# AuArd_1.net
KiCad netlist of a schematic drawn in Altium Designer
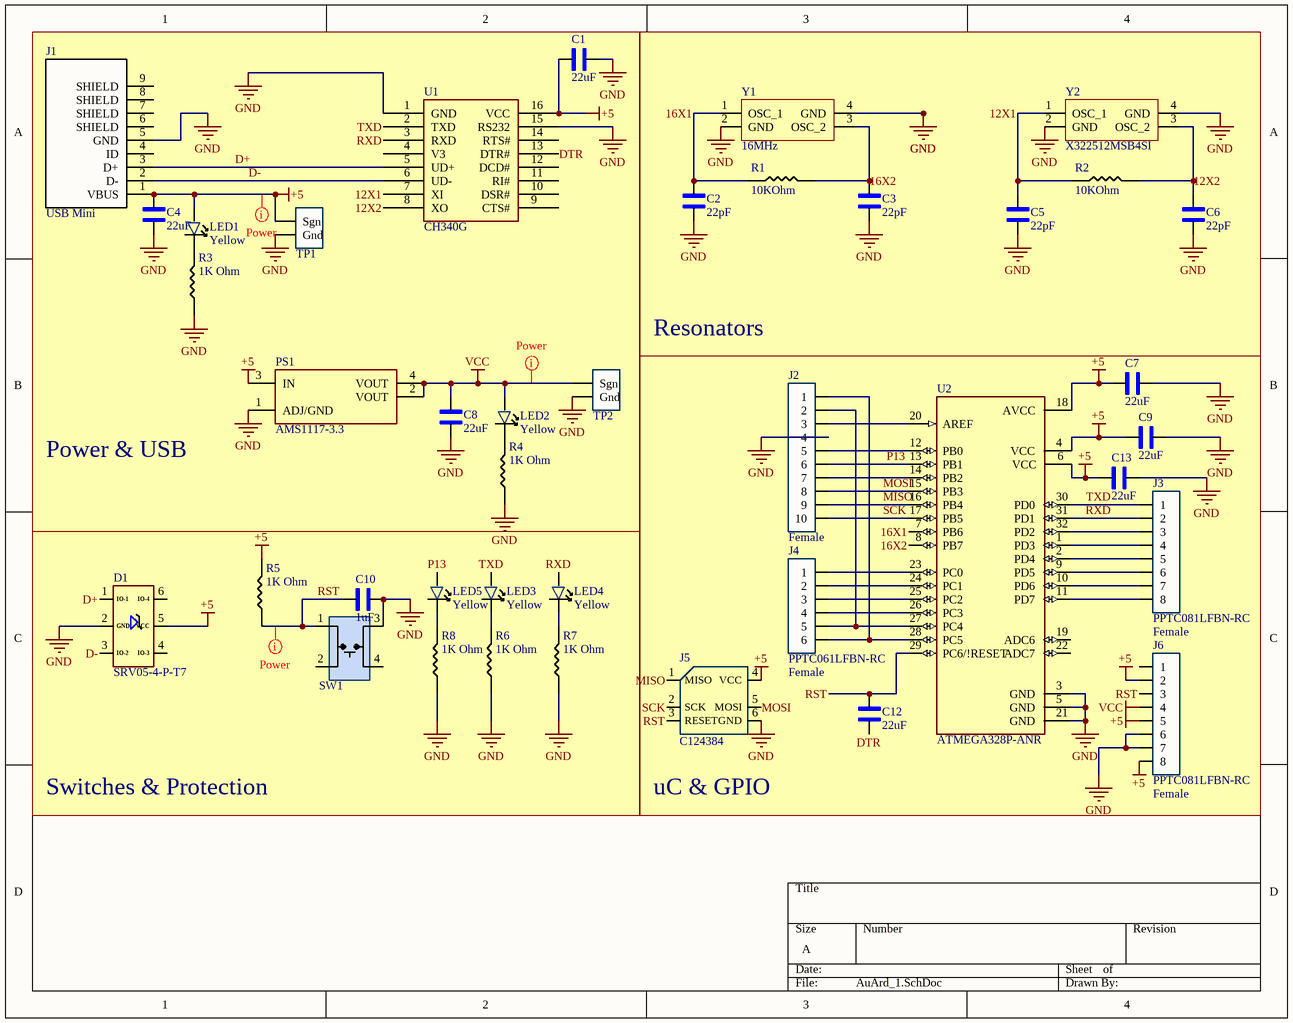
[diagram p0: AuArd_1.SchDoc]

(export (version "E")
  (design (tool "Eeschema 10.0.6"))
  (components
    (comp (ref "C1")
      (value "22uF")
      (footprint "1206_Passive_Capacitor")
      (description "22uF ±10% 25V X5R 1206 Multilayer Ceramic Capacitors MLCC - SMD/SMT RoHS")
      (fields (field (name "MFR PART #") "CL31A226KAHNNNE") (field (name "LCSC PART#") "C12891"))
      (libsource (lib "ECEN5730Lib_JLC_2021_08") (part "C_22uF_1206"))
    )
    (comp (ref "C2")
      (value "22pF")
      (footprint "1206_Passive_Capacitor")
      (description "22pF ±5% 1kV C0G 1206 Multilayer Ceramic Capacitors MLCC - SMD/SMT RoHS")
      (fields (field (name "LCSC PART#") "C313096") (field (name "MFR PART #") "1206CG220J102NT"))
      (libsource (lib "ECEN5730Lib_JLC_2021_08") (part "C_22pF_1206"))
    )
    (comp (ref "C3")
      (value "22pF")
      (footprint "1206_Passive_Capacitor")
      (description "22pF ±5% 1kV C0G 1206 Multilayer Ceramic Capacitors MLCC - SMD/SMT RoHS")
      (fields (field (name "LCSC PART#") "C313096") (field (name "MFR PART #") "1206CG220J102NT"))
      (libsource (lib "ECEN5730Lib_JLC_2021_08") (part "C_22pF_1206"))
    )
    (comp (ref "C4")
      (value "22uF")
      (footprint "1206_Passive_Capacitor")
      (description "22uF ±10% 25V X5R 1206 Multilayer Ceramic Capacitors MLCC - SMD/SMT RoHS")
      (fields (field (name "MFR PART #") "CL31A226KAHNNNE") (field (name "LCSC PART#") "C12891"))
      (libsource (lib "ECEN5730Lib_JLC_2021_08") (part "C_22uF_1206"))
    )
    (comp (ref "C5")
      (value "22pF")
      (footprint "1206_Passive_Capacitor")
      (description "22pF ±5% 1kV C0G 1206 Multilayer Ceramic Capacitors MLCC - SMD/SMT RoHS")
      (fields (field (name "LCSC PART#") "C313096") (field (name "MFR PART #") "1206CG220J102NT"))
      (libsource (lib "ECEN5730Lib_JLC_2021_08") (part "C_22pF_1206"))
    )
    (comp (ref "C6")
      (value "22pF")
      (footprint "1206_Passive_Capacitor")
      (description "22pF ±5% 1kV C0G 1206 Multilayer Ceramic Capacitors MLCC - SMD/SMT RoHS")
      (fields (field (name "LCSC PART#") "C313096") (field (name "MFR PART #") "1206CG220J102NT"))
      (libsource (lib "ECEN5730Lib_JLC_2021_08") (part "C_22pF_1206"))
    )
    (comp (ref "C7")
      (value "22uF")
      (footprint "1206_Passive_Capacitor")
      (description "22uF ±10% 25V X5R 1206 Multilayer Ceramic Capacitors MLCC - SMD/SMT RoHS")
      (fields (field (name "MFR PART #") "CL31A226KAHNNNE") (field (name "LCSC PART#") "C12891"))
      (libsource (lib "ECEN5730Lib_JLC_2021_08") (part "C_22uF_1206"))
    )
    (comp (ref "C8")
      (value "22uF")
      (footprint "1206_Passive_Capacitor")
      (description "22uF ±10% 25V X5R 1206 Multilayer Ceramic Capacitors MLCC - SMD/SMT RoHS")
      (fields (field (name "MFR PART #") "CL31A226KAHNNNE") (field (name "LCSC PART#") "C12891"))
      (libsource (lib "ECEN5730Lib_JLC_2021_08") (part "C_22uF_1206"))
    )
    (comp (ref "C9")
      (value "22uF")
      (footprint "1206_Passive_Capacitor")
      (description "22uF ±10% 25V X5R 1206 Multilayer Ceramic Capacitors MLCC - SMD/SMT RoHS")
      (fields (field (name "MFR PART #") "CL31A226KAHNNNE") (field (name "LCSC PART#") "C12891"))
      (libsource (lib "ECEN5730Lib_JLC_2021_08") (part "C_22uF_1206"))
    )
    (comp (ref "C10")
      (value "1uF")
      (footprint "1206_Passive_Capacitor")
      (description "MULTILAYER CERAMIC CAPACITORS MLCC - SMD/SMT 1UF 50V 1206 ROHS")
      (fields (field (name "DIGIKEY PART") "399-8150-1-ND") (field (name "MFR PART #") "CL31B105KBHNNNE"))
      (libsource (lib "ECEN5730Lib_JLC_2021_08") (part "C_1uF_1206"))
    )
    (comp (ref "C12")
      (value "22uF")
      (footprint "1206_Passive_Capacitor")
      (description "22uF ±10% 25V X5R 1206 Multilayer Ceramic Capacitors MLCC - SMD/SMT RoHS")
      (fields (field (name "MFR PART #") "CL31A226KAHNNNE") (field (name "LCSC PART#") "C12891"))
      (libsource (lib "ECEN5730Lib_JLC_2021_08") (part "C_22uF_1206"))
    )
    (comp (ref "C13")
      (value "22uF")
      (footprint "1206_Passive_Capacitor")
      (description "22uF ±10% 25V X5R 1206 Multilayer Ceramic Capacitors MLCC - SMD/SMT RoHS")
      (fields (field (name "MFR PART #") "CL31A226KAHNNNE") (field (name "LCSC PART#") "C12891"))
      (libsource (lib "ECEN5730Lib_JLC_2021_08") (part "C_22uF_1206"))
    )
    (comp (ref "D1")
      (value "SRV05-4-P-T7")
      (footprint "TVS")
      (description "TVS SOT-23-6 ROHS")
      (fields (field (name "LCSC PART#") "C85364"))
      (libsource (lib "ECEN5730Lib_JLC_2021_08") (part "D_TVS_Diode"))
    )
    (comp (ref "J1")
      (value "USB Mini")
      (footprint "USB_MINI_B")
      (description "Through Hole USB Connectors RoHS")
      (fields (field (name "LCSC PART#") "C46398") (field (name "MFR PART #") "920-462A2021D10102"))
      (libsource (lib "ECEN5730Lib_JLC_2021_08") (part "J_USB_B_Mini"))
    )
    (comp (ref "J2")
      (value "Female")
      (footprint "10_PIN_ARDUINO_100MIL")
      (description "10 Position Header Connector 0.100\" (2.54mm) Through Hole Tin")
      (fields (field (name "DIGIKEY PART") "S7008-ND") (field (name "LCSC PART#") "C225507"))
      (libsource (lib "ECEN5730Lib_JLC_2021_08") (part "JF_10_PIN_FEMALE_ARDUINO"))
    )
    (comp (ref "J3")
      (value "PPTC081LFBN-RC")
      (footprint "8_PIN_ARDUINO_100MIL")
      (description "8 Position Header Connector 0.100\" (2.54mm) Through Hole Tin")
      (fields
        (field (name "DIGIKEY PART") "S7006-ND")
        (field (name "LCSC PART#") "C27438")
        (field (name "ALTIUM_VALUE") "Female")
      )
      (libsource (lib "ECEN5730Lib_JLC_2021_08") (part "JF_8_PIN_FEMALE_ARDUINO"))
    )
    (comp (ref "J4")
      (value "PPTC061LFBN-RC")
      (footprint "6_PIN_ARDUINO_100mil")
      (description "6 Position Header Connector 0.100\" (2.54mm) Through Hole Tin")
      (fields
        (field (name "DIGIKEY PART") "S7004-ND")
        (field (name "LCSC PART#") "C40877")
        (field (name "ALTIUM_VALUE") "Female")
      )
      (libsource (lib "ECEN5730Lib_JLC_2021_08") (part "JF_6_PIN_FEMALE_ARDUINO"))
    )
    (comp (ref "J5")
      (value "NRPN032PAEN-RC")
      (footprint "ICSP")
      (description "Connector Header Through Hole 6 position 0.079\" (2.00mm)")
      (fields (field (name "DIGIKEY PART") "S5801-03-ND") (field (name "LCSC PART#") "C124384"))
      (libsource (lib "ECEN5730Lib_JLC_2021_08") (part "J_ICSP"))
    )
    (comp (ref "J6")
      (value "PPTC081LFBN-RC")
      (footprint "8_PIN_ARDUINO_100MIL")
      (description "8 Position Header Connector 0.100\" (2.54mm) Through Hole Tin")
      (fields
        (field (name "DIGIKEY PART") "S7006-ND")
        (field (name "LCSC PART#") "C27438")
        (field (name "ALTIUM_VALUE") "Female")
      )
      (libsource (lib "ECEN5730Lib_JLC_2021_08") (part "JF_8_PIN_FEMALE_ARDUINO"))
    )
    (comp (ref "LED1")
      (value "Yellow")
      (footprint "LED_0603")
      (description "LIGHT EMITTING DIODES (LED) YELLOW 585.5~591.5NM 90~180MCD@20MA TOP VIEW 0603 ROHS")
      (fields (field (name "MFR PART #") "19-213/Y2C-CQ2R2L/3T(CY)") (field (name "LCSC PART#") "C72038"))
      (libsource (lib "ECEN5730Lib_JLC_2021_08") (part "LED_YELLOW_0603"))
    )
    (comp (ref "LED2")
      (value "Yellow")
      (footprint "LED_0603")
      (description "LIGHT EMITTING DIODES (LED) YELLOW 585.5~591.5NM 90~180MCD@20MA TOP VIEW 0603 ROHS")
      (fields (field (name "MFR PART #") "19-213/Y2C-CQ2R2L/3T(CY)") (field (name "LCSC PART#") "C72038"))
      (libsource (lib "ECEN5730Lib_JLC_2021_08") (part "LED_YELLOW_0603"))
    )
    (comp (ref "LED3")
      (value "Yellow")
      (footprint "LED_0603")
      (description "LIGHT EMITTING DIODES (LED) YELLOW 585.5~591.5NM 90~180MCD@20MA TOP VIEW 0603 ROHS")
      (fields (field (name "MFR PART #") "19-213/Y2C-CQ2R2L/3T(CY)") (field (name "LCSC PART#") "C72038"))
      (libsource (lib "ECEN5730Lib_JLC_2021_08") (part "LED_YELLOW_0603"))
    )
    (comp (ref "LED4")
      (value "Yellow")
      (footprint "LED_0603")
      (description "LIGHT EMITTING DIODES (LED) YELLOW 585.5~591.5NM 90~180MCD@20MA TOP VIEW 0603 ROHS")
      (fields (field (name "MFR PART #") "19-213/Y2C-CQ2R2L/3T(CY)") (field (name "LCSC PART#") "C72038"))
      (libsource (lib "ECEN5730Lib_JLC_2021_08") (part "LED_YELLOW_0603"))
    )
    (comp (ref "LED5")
      (value "Yellow")
      (footprint "LED_0603")
      (description "LIGHT EMITTING DIODES (LED) YELLOW 585.5~591.5NM 90~180MCD@20MA TOP VIEW 0603 ROHS")
      (fields (field (name "MFR PART #") "19-213/Y2C-CQ2R2L/3T(CY)") (field (name "LCSC PART#") "C72038"))
      (libsource (lib "ECEN5730Lib_JLC_2021_08") (part "LED_YELLOW_0603"))
    )
    (comp (ref "PS1")
      (value "AMS1117-3.3")
      (footprint "LDO")
      (description "LOW DROPOUT REGULATORS(LDO) POSITIVE FIXED 1.3V @ 800MA 15V 3.3V 1A SOT-223 ROHS")
      (fields (field (name "LCSC PART#") "C6186"))
      (libsource (lib "ECEN5730Lib_JLC_2021_08") (part "PS_AMS_LDO_3v3"))
    )
    (comp (ref "R1")
      (value "10KOhm")
      (footprint "1206_Passive_Resitor")
      (description "10 kOhms ±5% 0.25W, 1/4W Chip Resistor 1206 (3216 Metric) Automotive AEC-Q200 Thick Film")
      (fields (field (name "DIGIKEY PART") "RMCF1206JT300RCT-ND") (field (name "LCSC PART#") "C17902"))
      (libsource (lib "ECEN5730Lib_JLC_2021_08") (part "R_10KOhm_1206"))
    )
    (comp (ref "R2")
      (value "10KOhm")
      (footprint "1206_Passive_Resitor")
      (description "10 kOhms ±5% 0.25W, 1/4W Chip Resistor 1206 (3216 Metric) Automotive AEC-Q200 Thick Film")
      (fields (field (name "DIGIKEY PART") "RMCF1206JT300RCT-ND") (field (name "LCSC PART#") "C17902"))
      (libsource (lib "ECEN5730Lib_JLC_2021_08") (part "R_10KOhm_1206"))
    )
    (comp (ref "R3")
      (value "1K Ohm")
      (footprint "1206_Passive_Resitor")
      (description "CHIP RESISTOR - SURFACE MOUNT 1KOHMS ±1% 1/4W 1206 ROHS")
      (fields (field (name "DIGIKEY PART") "RNCP1206FTD1K00CT-ND") (field (name "LCSC PART#") "C4410"))
      (libsource (lib "ECEN5730Lib_JLC_2021_08") (part "R_1K_1206"))
    )
    (comp (ref "R4")
      (value "1K Ohm")
      (footprint "1206_Passive_Resitor")
      (description "CHIP RESISTOR - SURFACE MOUNT 1KOHMS ±1% 1/4W 1206 ROHS")
      (fields (field (name "DIGIKEY PART") "RNCP1206FTD1K00CT-ND") (field (name "LCSC PART#") "C4410"))
      (libsource (lib "ECEN5730Lib_JLC_2021_08") (part "R_1K_1206"))
    )
    (comp (ref "R5")
      (value "1K Ohm")
      (footprint "1206_Passive_Resitor")
      (description "CHIP RESISTOR - SURFACE MOUNT 1KOHMS ±1% 1/4W 1206 ROHS")
      (fields (field (name "DIGIKEY PART") "RNCP1206FTD1K00CT-ND") (field (name "LCSC PART#") "C4410"))
      (libsource (lib "ECEN5730Lib_JLC_2021_08") (part "R_1K_1206"))
    )
    (comp (ref "R6")
      (value "1K Ohm")
      (footprint "1206_Passive_Resitor")
      (description "CHIP RESISTOR - SURFACE MOUNT 1KOHMS ±1% 1/4W 1206 ROHS")
      (fields (field (name "DIGIKEY PART") "RNCP1206FTD1K00CT-ND") (field (name "LCSC PART#") "C4410"))
      (libsource (lib "ECEN5730Lib_JLC_2021_08") (part "R_1K_1206"))
    )
    (comp (ref "R7")
      (value "1K Ohm")
      (footprint "1206_Passive_Resitor")
      (description "CHIP RESISTOR - SURFACE MOUNT 1KOHMS ±1% 1/4W 1206 ROHS")
      (fields (field (name "DIGIKEY PART") "RNCP1206FTD1K00CT-ND") (field (name "LCSC PART#") "C4410"))
      (libsource (lib "ECEN5730Lib_JLC_2021_08") (part "R_1K_1206"))
    )
    (comp (ref "R8")
      (value "1K Ohm")
      (footprint "1206_Passive_Resitor")
      (description "CHIP RESISTOR - SURFACE MOUNT 1KOHMS ±1% 1/4W 1206 ROHS")
      (fields (field (name "DIGIKEY PART") "RNCP1206FTD1K00CT-ND") (field (name "LCSC PART#") "C4410"))
      (libsource (lib "ECEN5730Lib_JLC_2021_08") (part "R_1K_1206"))
    )
    (comp (ref "SW1")
      (value "TL3305AF160QG")
      (footprint "Switch_JLC")
      (description "Tactile Switch SPST-NO Top Actuated Surface Mount")
      (fields (field (name "MFR PART #") "C174049"))
      (libsource (lib "ECEN5730Lib_JLC_2021_08") (part "SW_Push_Button_JLC"))
    )
    (comp (ref "TP1")
      (value "10x Probe TP")
      (footprint "TP10x_Probe")
      (description "Test Point 300 mil centers")
      (libsource (lib "ECEN5730Lib_Manual_2021_08") (part "TP_10x_Probe"))
    )
    (comp (ref "TP2")
      (value "10x Probe TP")
      (footprint "TP10x_Probe")
      (description "Test Point 300 mil centers")
      (libsource (lib "ECEN5730Lib_Manual_2021_08") (part "TP_10x_Probe"))
    )
    (comp (ref "U1")
      (value "CH340G")
      (footprint "USB to serial")
      (description "Transceiver USB 2.0 2Mbps SOP-16_150mil USB ICs RoHS")
      (fields (field (name "LCSC PART#") "C14267"))
      (libsource (lib "ECEN5730Lib_JLC_2021_08") (part "U_USBtoSerial"))
    )
    (comp (ref "U2")
      (value "ATMEGA328P-ANR")
      (footprint "ATMega328P")
      (description "AVR AVR® ATmega Microcontroller IC 8-Bit 20MHz 32KB (16K x 16) FLASH 32-TQFP (7x7)")
      (fields (field (name "MFR PART #") "ATMEGA328P-AU") (field (name "LCSC PART#") "C14877"))
      (libsource (lib "ECEN5730Lib_JLC_2021_08") (part "U_ATMega328P"))
    )
    (comp (ref "Y1")
      (value "16MHz")
      (footprint "Crystal resonator")
      (description "±10ppm 16000000Hz -40℃~85℃ 贴片无源晶振 60Ω 9pF SMD3225-4P Crystals ROHS")
      (fields (field (name "LCSC PART#") "C13738") (field (name "MFR PART #") "X322516MLB4SI"))
      (libsource (lib "ECEN5730Lib_JLC_2021_08") (part "X_16Mhz_Res"))
    )
    (comp (ref "Y2")
      (value "X322512MSB4SI")
      (footprint "Crystal resonator")
      (description "SMD Crystal Resonators 12MHz ±10ppm SMD-3225_4P RoHS")
      (fields (field (name "LCSC PART#") "C9002"))
      (libsource (lib "ECEN5730Lib_JLC_2021_08") (part "X_12MHz_Res"))
    )
  )
  (nets
    (net (code "1") (name "+5") (class "Default")
      (node (ref "C1") (pin "2") (pinfunction "2_2") (pintype "passive"))
      (node (ref "C13") (pin "2") (pinfunction "2_2") (pintype "passive"))
      (node (ref "C4") (pin "2") (pinfunction "2_2") (pintype "passive"))
      (node (ref "C7") (pin "2") (pinfunction "2_2") (pintype "passive"))
      (node (ref "C9") (pin "2") (pinfunction "2_2") (pintype "passive"))
      (node (ref "D1") (pin "5") (pinfunction "VCC_5") (pintype "passive"))
      (node (ref "J1") (pin "1") (pinfunction "VBUS_1") (pintype "passive"))
      (node (ref "J5") (pin "4") (pinfunction "VCC_4") (pintype "passive"))
      (node (ref "J6") (pin "2") (pinfunction "2_2") (pintype "passive"))
      (node (ref "J6") (pin "5") (pinfunction "5_5") (pintype "passive"))
      (node (ref "J6") (pin "8") (pinfunction "8_8") (pintype "passive"))
      (node (ref "LED1") (pin "1") (pinfunction "1_1") (pintype "passive"))
      (node (ref "PS1") (pin "3") (pinfunction "IN_3") (pintype "power_in"))
      (node (ref "R5") (pin "2") (pinfunction "2_2") (pintype "passive"))
      (node (ref "TP1") (pin "1") (pinfunction "Sgn_1") (pintype "passive"))
      (node (ref "U1") (pin "16") (pinfunction "VCC_16") (pintype "passive"))
      (node (ref "U2") (pin "18") (pinfunction "AVCC_18") (pintype "power_in"))
      (node (ref "U2") (pin "4") (pinfunction "VCC_4") (pintype "power_in"))
      (node (ref "U2") (pin "6") (pinfunction "VCC_6") (pintype "power_in"))
    )
    (net (code "2") (name "/12X1") (class "Default")
      (node (ref "C5") (pin "2") (pinfunction "2_2") (pintype "passive"))
      (node (ref "R2") (pin "1") (pinfunction "1_1") (pintype "passive"))
      (node (ref "U1") (pin "7") (pinfunction "XI_7") (pintype "passive"))
      (node (ref "Y2") (pin "1") (pinfunction "OSC_1_1") (pintype "passive"))
    )
    (net (code "3") (name "/12X2") (class "Default")
      (node (ref "C6") (pin "2") (pinfunction "2_2") (pintype "passive"))
      (node (ref "R2") (pin "2") (pinfunction "2_2") (pintype "passive"))
      (node (ref "U1") (pin "8") (pinfunction "XO_8") (pintype "passive"))
      (node (ref "Y2") (pin "3") (pinfunction "OSC_2_3") (pintype "passive"))
    )
    (net (code "4") (name "/16X1") (class "Default")
      (node (ref "C2") (pin "2") (pinfunction "2_2") (pintype "passive"))
      (node (ref "R1") (pin "1") (pinfunction "1_1") (pintype "passive"))
      (node (ref "U2") (pin "7") (pinfunction "PB6_7") (pintype "bidirectional"))
      (node (ref "Y1") (pin "1") (pinfunction "OSC_1_1") (pintype "passive"))
    )
    (net (code "5") (name "/16X2") (class "Default")
      (node (ref "C3") (pin "2") (pinfunction "2_2") (pintype "passive"))
      (node (ref "R1") (pin "2") (pinfunction "2_2") (pintype "passive"))
      (node (ref "U2") (pin "8") (pinfunction "PB7_8") (pintype "bidirectional"))
      (node (ref "Y1") (pin "3") (pinfunction "OSC_2_3") (pintype "passive"))
    )
    (net (code "6") (name "/D+") (class "Default")
      (node (ref "D1") (pin "1") (pinfunction "IO-1_1") (pintype "passive"))
      (node (ref "J1") (pin "3") (pinfunction "D+_3") (pintype "passive"))
      (node (ref "U1") (pin "5") (pinfunction "UD+_5") (pintype "passive"))
    )
    (net (code "7") (name "/D-") (class "Default")
      (node (ref "D1") (pin "3") (pinfunction "IO-2_3") (pintype "passive"))
      (node (ref "J1") (pin "2") (pinfunction "D-_2") (pintype "passive"))
      (node (ref "U1") (pin "6") (pinfunction "UD-_6") (pintype "passive"))
    )
    (net (code "8") (name "/DTR") (class "Default")
      (node (ref "C12") (pin "1") (pinfunction "1_1") (pintype "passive"))
      (node (ref "U1") (pin "13") (pinfunction "DTR#_13") (pintype "passive"))
    )
    (net (code "9") (name "/MISO") (class "Default")
      (node (ref "J2") (pin "9") (pinfunction "9_9") (pintype "passive"))
      (node (ref "J5") (pin "1") (pinfunction "MISO_1") (pintype "passive"))
      (node (ref "U2") (pin "16") (pinfunction "PB4_16") (pintype "bidirectional"))
    )
    (net (code "10") (name "/MOSI") (class "Default")
      (node (ref "J2") (pin "8") (pinfunction "8_8") (pintype "passive"))
      (node (ref "J5") (pin "5") (pinfunction "MOSI_5") (pintype "passive"))
      (node (ref "U2") (pin "15") (pinfunction "PB3_15") (pintype "bidirectional"))
    )
    (net (code "11") (name "/P13") (class "Default")
      (node (ref "J2") (pin "6") (pinfunction "6_6") (pintype "passive"))
      (node (ref "LED5") (pin "1") (pinfunction "1_1") (pintype "passive"))
      (node (ref "U2") (pin "13") (pinfunction "PB1_13") (pintype "bidirectional"))
    )
    (net (code "12") (name "/RST") (class "Default")
      (node (ref "C10") (pin "1") (pinfunction "1_1") (pintype "passive"))
      (node (ref "C12") (pin "2") (pinfunction "2_2") (pintype "passive"))
      (node (ref "J5") (pin "3") (pinfunction "RESET_3") (pintype "passive"))
      (node (ref "J6") (pin "3") (pinfunction "3_3") (pintype "passive"))
      (node (ref "R5") (pin "1") (pinfunction "1_1") (pintype "passive"))
      (node (ref "SW1") (pin "1") (pinfunction "1_1") (pintype "passive"))
      (node (ref "U2") (pin "29") (pinfunction "PC6/!RESET_29") (pintype "bidirectional"))
    )
    (net (code "13") (name "/RXD") (class "Default")
      (node (ref "J3") (pin "2") (pinfunction "2_2") (pintype "passive"))
      (node (ref "LED4") (pin "1") (pinfunction "1_1") (pintype "passive"))
      (node (ref "U1") (pin "3") (pinfunction "RXD_3") (pintype "passive"))
      (node (ref "U2") (pin "31") (pinfunction "PD1_31") (pintype "bidirectional"))
    )
    (net (code "14") (name "/SCK") (class "Default")
      (node (ref "J2") (pin "10") (pinfunction "10_10") (pintype "passive"))
      (node (ref "J5") (pin "2") (pinfunction "SCK_2") (pintype "passive"))
      (node (ref "U2") (pin "17") (pinfunction "PB5_17") (pintype "bidirectional"))
    )
    (net (code "15") (name "/TXD") (class "Default")
      (node (ref "J3") (pin "1") (pinfunction "1_1") (pintype "passive"))
      (node (ref "LED3") (pin "1") (pinfunction "1_1") (pintype "passive"))
      (node (ref "U1") (pin "2") (pinfunction "TXD_2") (pintype "passive"))
      (node (ref "U2") (pin "30") (pinfunction "PD0_30") (pintype "bidirectional"))
    )
    (net (code "16") (name "GND") (class "Default")
      (node (ref "C1") (pin "1") (pinfunction "1_1") (pintype "passive"))
      (node (ref "C10") (pin "2") (pinfunction "2_2") (pintype "passive"))
      (node (ref "C13") (pin "1") (pinfunction "1_1") (pintype "passive"))
      (node (ref "C2") (pin "1") (pinfunction "1_1") (pintype "passive"))
      (node (ref "C3") (pin "1") (pinfunction "1_1") (pintype "passive"))
      (node (ref "C4") (pin "1") (pinfunction "1_1") (pintype "passive"))
      (node (ref "C5") (pin "1") (pinfunction "1_1") (pintype "passive"))
      (node (ref "C6") (pin "1") (pinfunction "1_1") (pintype "passive"))
      (node (ref "C7") (pin "1") (pinfunction "1_1") (pintype "passive"))
      (node (ref "C8") (pin "1") (pinfunction "1_1") (pintype "passive"))
      (node (ref "C9") (pin "1") (pinfunction "1_1") (pintype "passive"))
      (node (ref "D1") (pin "2") (pinfunction "GND_2") (pintype "passive"))
      (node (ref "J1") (pin "5") (pinfunction "GND_5") (pintype "passive"))
      (node (ref "J2") (pin "4") (pinfunction "4_4") (pintype "passive"))
      (node (ref "J5") (pin "6") (pinfunction "GND_6") (pintype "passive"))
      (node (ref "J6") (pin "6") (pinfunction "6_6") (pintype "passive"))
      (node (ref "J6") (pin "7") (pinfunction "7_7") (pintype "passive"))
      (node (ref "PS1") (pin "1") (pinfunction "ADJ/GND_1") (pintype "passive"))
      (node (ref "R3") (pin "1") (pinfunction "1_1") (pintype "passive"))
      (node (ref "R4") (pin "1") (pinfunction "1_1") (pintype "passive"))
      (node (ref "R6") (pin "1") (pinfunction "1_1") (pintype "passive"))
      (node (ref "R7") (pin "1") (pinfunction "1_1") (pintype "passive"))
      (node (ref "R8") (pin "1") (pinfunction "1_1") (pintype "passive"))
      (node (ref "SW1") (pin "3") (pinfunction "3_3") (pintype "passive"))
      (node (ref "TP1") (pin "2") (pinfunction "Gnd_2") (pintype "passive"))
      (node (ref "TP2") (pin "2") (pinfunction "Gnd_2") (pintype "passive"))
      (node (ref "U1") (pin "1") (pinfunction "GND_1") (pintype "passive"))
      (node (ref "U1") (pin "15") (pinfunction "RS232_15") (pintype "passive"))
      (node (ref "U2") (pin "21") (pinfunction "GND_21") (pintype "power_in"))
      (node (ref "U2") (pin "3") (pinfunction "GND_3") (pintype "power_in"))
      (node (ref "U2") (pin "5") (pinfunction "GND_5") (pintype "power_in"))
      (node (ref "Y1") (pin "2") (pinfunction "GND_2") (pintype "passive"))
      (node (ref "Y1") (pin "4") (pinfunction "GND_4") (pintype "passive"))
      (node (ref "Y2") (pin "2") (pinfunction "GND_2") (pintype "passive"))
      (node (ref "Y2") (pin "4") (pinfunction "GND_4") (pintype "passive"))
    )
    (net (code "17") (name "Net-(LED1-Pad2)") (class "Default")
      (node (ref "LED1") (pin "2") (pinfunction "2_2") (pintype "passive"))
      (node (ref "R3") (pin "2") (pinfunction "2_2") (pintype "passive"))
    )
    (net (code "18") (name "Net-(LED2-Pad2)") (class "Default")
      (node (ref "LED2") (pin "2") (pinfunction "2_2") (pintype "passive"))
      (node (ref "R4") (pin "2") (pinfunction "2_2") (pintype "passive"))
    )
    (net (code "19") (name "Net-(LED3-Pad2)") (class "Default")
      (node (ref "LED3") (pin "2") (pinfunction "2_2") (pintype "passive"))
      (node (ref "R6") (pin "2") (pinfunction "2_2") (pintype "passive"))
    )
    (net (code "20") (name "Net-(LED4-Pad2)") (class "Default")
      (node (ref "LED4") (pin "2") (pinfunction "2_2") (pintype "passive"))
      (node (ref "R7") (pin "2") (pinfunction "2_2") (pintype "passive"))
    )
    (net (code "21") (name "Net-(LED5-Pad2)") (class "Default")
      (node (ref "LED5") (pin "2") (pinfunction "2_2") (pintype "passive"))
      (node (ref "R8") (pin "2") (pinfunction "2_2") (pintype "passive"))
    )
    (net (code "22") (name "Net-(U2-AREF)") (class "Default")
      (node (ref "J2") (pin "3") (pinfunction "3_3") (pintype "passive"))
      (node (ref "U2") (pin "20") (pinfunction "AREF_20") (pintype "input"))
    )
    (net (code "23") (name "Net-(U2-PB0)") (class "Default")
      (node (ref "J2") (pin "5") (pinfunction "5_5") (pintype "passive"))
      (node (ref "U2") (pin "12") (pinfunction "PB0_12") (pintype "bidirectional"))
    )
    (net (code "24") (name "Net-(U2-PB2)") (class "Default")
      (node (ref "J2") (pin "7") (pinfunction "7_7") (pintype "passive"))
      (node (ref "U2") (pin "14") (pinfunction "PB2_14") (pintype "bidirectional"))
    )
    (net (code "25") (name "Net-(U2-PC0)") (class "Default")
      (node (ref "J4") (pin "1") (pinfunction "1_1") (pintype "passive"))
      (node (ref "U2") (pin "23") (pinfunction "PC0_23") (pintype "bidirectional"))
    )
    (net (code "26") (name "Net-(U2-PC1)") (class "Default")
      (node (ref "J4") (pin "2") (pinfunction "2_2") (pintype "passive"))
      (node (ref "U2") (pin "24") (pinfunction "PC1_24") (pintype "bidirectional"))
    )
    (net (code "27") (name "Net-(U2-PC2)") (class "Default")
      (node (ref "J4") (pin "3") (pinfunction "3_3") (pintype "passive"))
      (node (ref "U2") (pin "25") (pinfunction "PC2_25") (pintype "bidirectional"))
    )
    (net (code "28") (name "Net-(U2-PC3)") (class "Default")
      (node (ref "J4") (pin "4") (pinfunction "4_4") (pintype "passive"))
      (node (ref "U2") (pin "26") (pinfunction "PC3_26") (pintype "bidirectional"))
    )
    (net (code "29") (name "Net-(U2-PC4)") (class "Default")
      (node (ref "J2") (pin "2") (pinfunction "2_2") (pintype "passive"))
      (node (ref "J4") (pin "5") (pinfunction "5_5") (pintype "passive"))
      (node (ref "U2") (pin "27") (pinfunction "PC4_27") (pintype "bidirectional"))
    )
    (net (code "30") (name "Net-(U2-PC5)") (class "Default")
      (node (ref "J2") (pin "1") (pinfunction "1_1") (pintype "passive"))
      (node (ref "J4") (pin "6") (pinfunction "6_6") (pintype "passive"))
      (node (ref "U2") (pin "28") (pinfunction "PC5_28") (pintype "bidirectional"))
    )
    (net (code "31") (name "Net-(U2-PD2)") (class "Default")
      (node (ref "J3") (pin "3") (pinfunction "3_3") (pintype "passive"))
      (node (ref "U2") (pin "32") (pinfunction "PD2_32") (pintype "bidirectional"))
    )
    (net (code "32") (name "Net-(U2-PD3)") (class "Default")
      (node (ref "J3") (pin "4") (pinfunction "4_4") (pintype "passive"))
      (node (ref "U2") (pin "1") (pinfunction "PD3_1") (pintype "bidirectional"))
    )
    (net (code "33") (name "Net-(U2-PD4)") (class "Default")
      (node (ref "J3") (pin "5") (pinfunction "5_5") (pintype "passive"))
      (node (ref "U2") (pin "2") (pinfunction "PD4_2") (pintype "bidirectional"))
    )
    (net (code "34") (name "Net-(U2-PD5)") (class "Default")
      (node (ref "J3") (pin "6") (pinfunction "6_6") (pintype "passive"))
      (node (ref "U2") (pin "9") (pinfunction "PD5_9") (pintype "bidirectional"))
    )
    (net (code "35") (name "Net-(U2-PD6)") (class "Default")
      (node (ref "J3") (pin "7") (pinfunction "7_7") (pintype "passive"))
      (node (ref "U2") (pin "10") (pinfunction "PD6_10") (pintype "bidirectional"))
    )
    (net (code "36") (name "Net-(U2-PD7)") (class "Default")
      (node (ref "J3") (pin "8") (pinfunction "8_8") (pintype "passive"))
      (node (ref "U2") (pin "11") (pinfunction "PD7_11") (pintype "bidirectional"))
    )
    (net (code "37") (name "VCC") (class "Default")
      (node (ref "C8") (pin "2") (pinfunction "2_2") (pintype "passive"))
      (node (ref "J6") (pin "4") (pinfunction "4_4") (pintype "passive"))
      (node (ref "LED2") (pin "1") (pinfunction "1_1") (pintype "passive"))
      (node (ref "PS1") (pin "2") (pinfunction "VOUT_2") (pintype "power_in"))
      (node (ref "PS1") (pin "4") (pinfunction "VOUT_4") (pintype "power_in"))
      (node (ref "TP2") (pin "1") (pinfunction "Sgn_1") (pintype "passive"))
    )
    (net (code "38") (name "unconnected-(D1-IO-3-Pad4)") (class "Default")
      (node (ref "D1") (pin "4") (pinfunction "IO-3_4") (pintype "passive"))
    )
    (net (code "39") (name "unconnected-(D1-IO-4-Pad6)") (class "Default")
      (node (ref "D1") (pin "6") (pinfunction "IO-4_6") (pintype "passive"))
    )
    (net (code "40") (name "unconnected-(J1-ID-Pad4)") (class "Default")
      (node (ref "J1") (pin "4") (pinfunction "ID_4") (pintype "passive"))
    )
    (net (code "41") (name "unconnected-(J1-SHIELD-Pad6)") (class "Default")
      (node (ref "J1") (pin "6") (pinfunction "SHIELD_6") (pintype "passive"))
    )
    (net (code "42") (name "unconnected-(J1-SHIELD-Pad7)") (class "Default")
      (node (ref "J1") (pin "7") (pinfunction "SHIELD_7") (pintype "passive"))
    )
    (net (code "43") (name "unconnected-(J1-SHIELD-Pad8)") (class "Default")
      (node (ref "J1") (pin "8") (pinfunction "SHIELD_8") (pintype "passive"))
    )
    (net (code "44") (name "unconnected-(J1-SHIELD-Pad9)") (class "Default")
      (node (ref "J1") (pin "9") (pinfunction "SHIELD_9") (pintype "passive"))
    )
    (net (code "45") (name "unconnected-(J6-Pad1)") (class "Default")
      (node (ref "J6") (pin "1") (pinfunction "1_1") (pintype "passive"))
    )
    (net (code "46") (name "unconnected-(SW1-Pad2)") (class "Default")
      (node (ref "SW1") (pin "2") (pinfunction "2_2") (pintype "passive"))
    )
    (net (code "47") (name "unconnected-(SW1-Pad4)") (class "Default")
      (node (ref "SW1") (pin "4") (pinfunction "4_4") (pintype "passive"))
    )
    (net (code "48") (name "unconnected-(U1-CTS#-Pad9)") (class "Default")
      (node (ref "U1") (pin "9") (pinfunction "CTS#_9") (pintype "passive"))
    )
    (net (code "49") (name "unconnected-(U1-DCD#-Pad12)") (class "Default")
      (node (ref "U1") (pin "12") (pinfunction "DCD#_12") (pintype "passive"))
    )
    (net (code "50") (name "unconnected-(U1-DSR#-Pad10)") (class "Default")
      (node (ref "U1") (pin "10") (pinfunction "DSR#_10") (pintype "passive"))
    )
    (net (code "51") (name "unconnected-(U1-RI#-Pad11)") (class "Default")
      (node (ref "U1") (pin "11") (pinfunction "RI#_11") (pintype "passive"))
    )
    (net (code "52") (name "unconnected-(U1-RTS#-Pad14)") (class "Default")
      (node (ref "U1") (pin "14") (pinfunction "RTS#_14") (pintype "passive"))
    )
    (net (code "53") (name "unconnected-(U1-V3-Pad4)") (class "Default")
      (node (ref "U1") (pin "4") (pinfunction "V3_4") (pintype "passive"))
    )
    (net (code "54") (name "unconnected-(U2-ADC6-Pad19)") (class "Default")
      (node (ref "U2") (pin "19") (pinfunction "ADC6_19") (pintype "bidirectional"))
    )
    (net (code "55") (name "unconnected-(U2-ADC7-Pad22)") (class "Default")
      (node (ref "U2") (pin "22") (pinfunction "ADC7_22") (pintype "bidirectional"))
    )
  )
)
